# GEF-USB-B.net
KiCad netlist of a schematic drawn in EAGLE
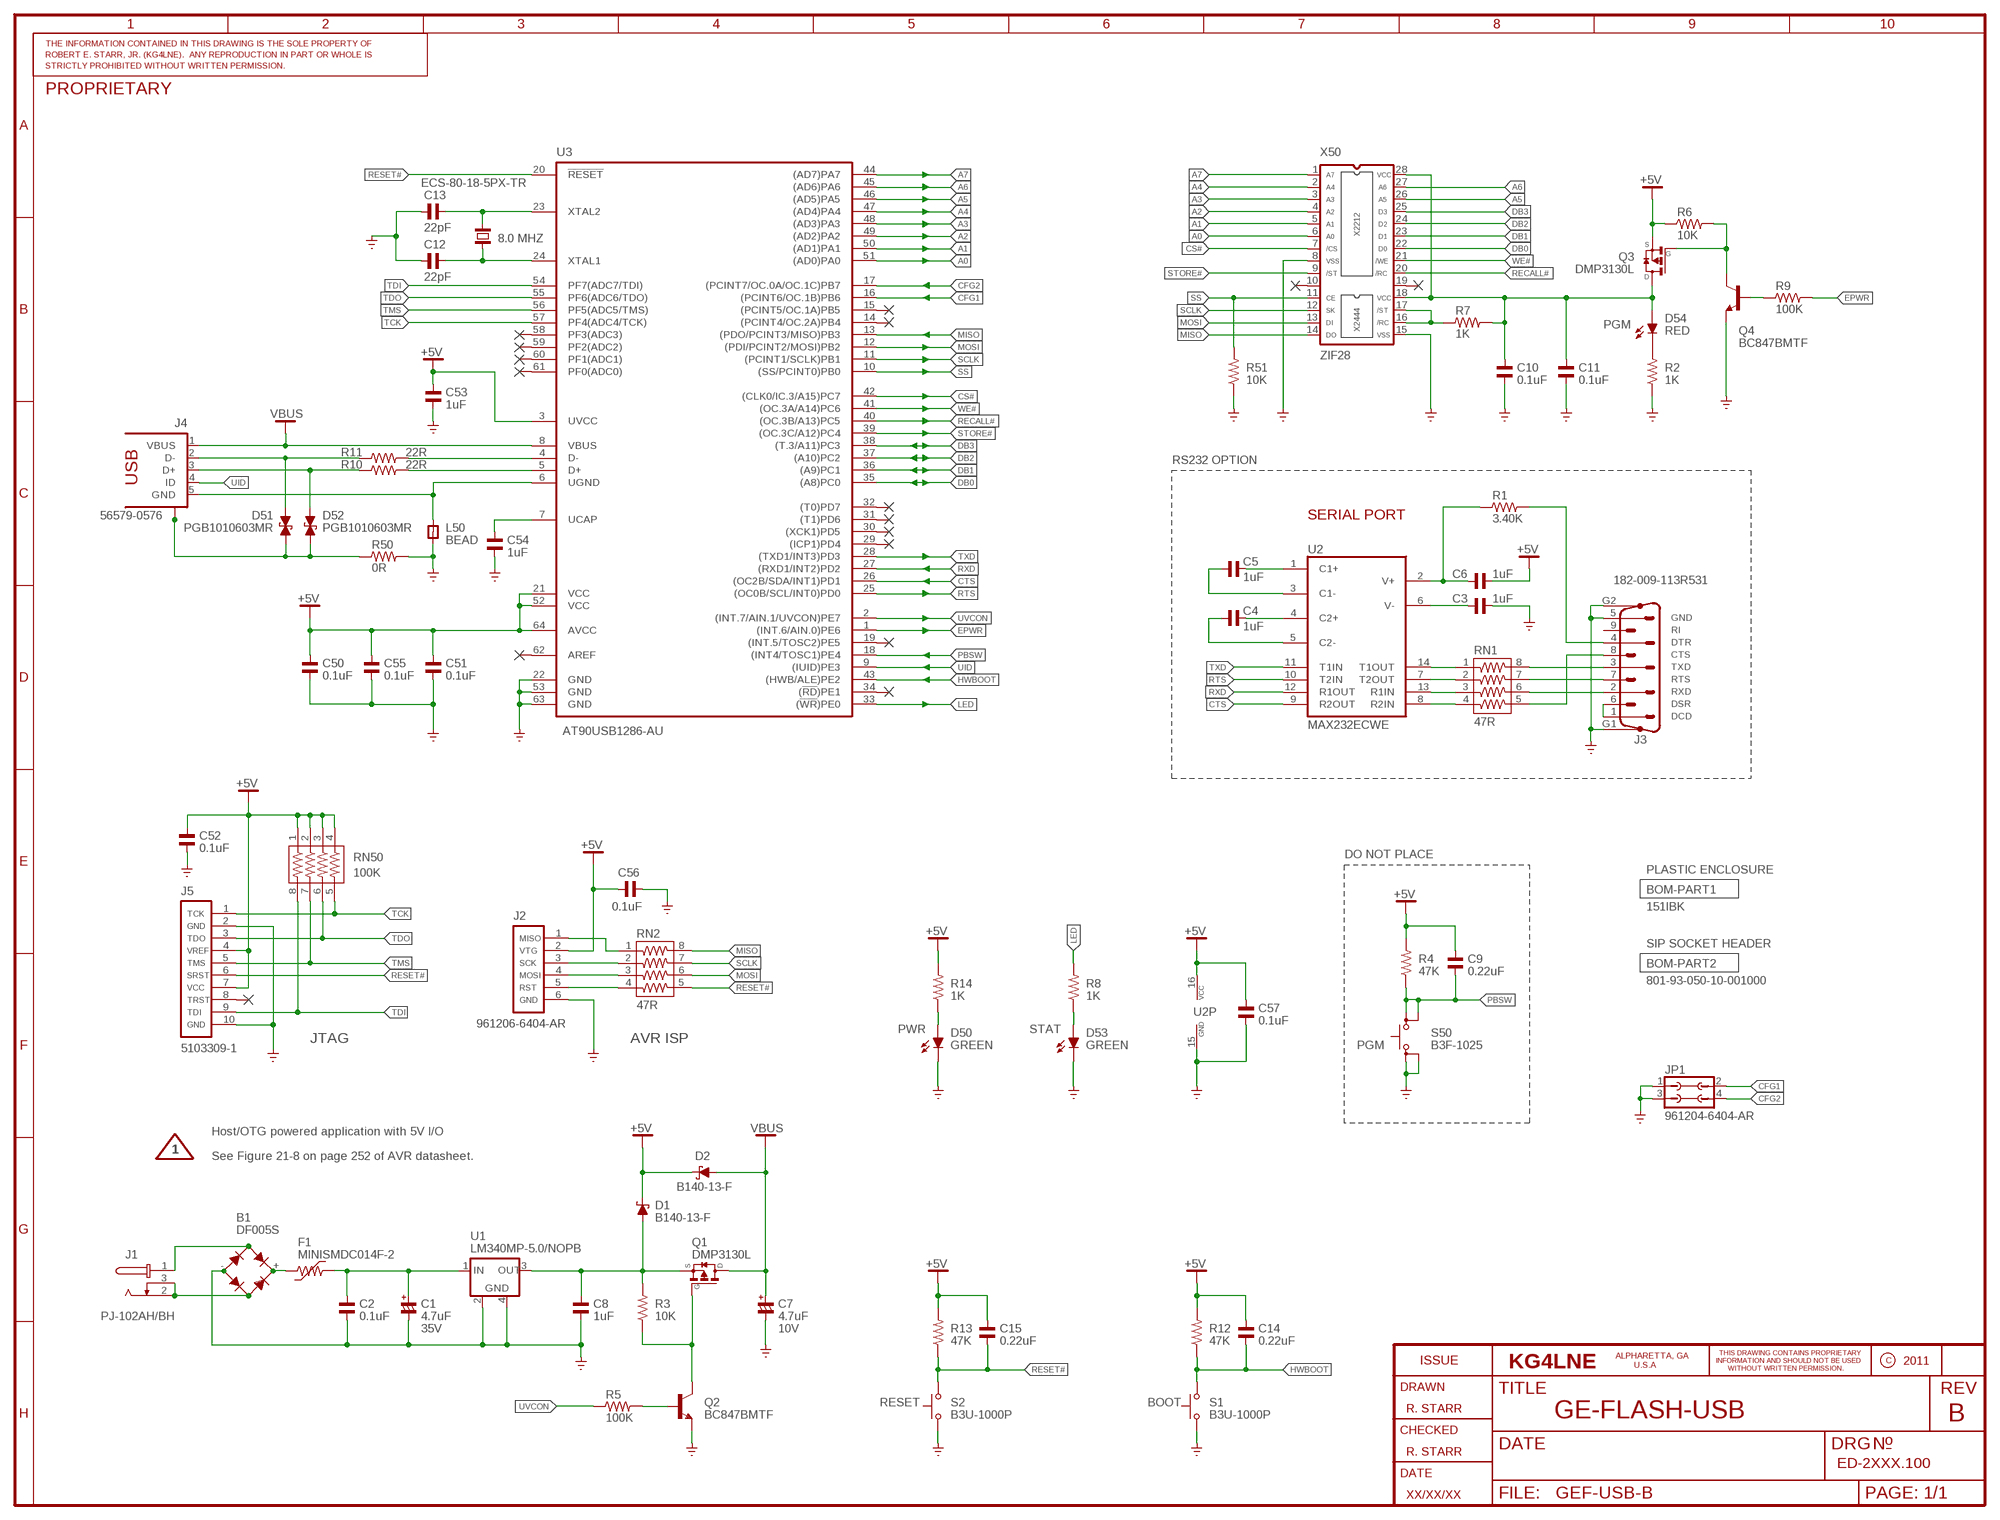
[diagram p0: schematic, sheet 1]

(export (version "E")
  (design (tool "Eeschema 10.0.6"))
  (components
    (comp (ref "B1")
      (value "DF005S")
      (footprint "eagle-import:DF-S")
      (libsource (lib "eagle-import") (part "DF-S"))
    )
    (comp (ref "C1")
      (value "4.7uF")
      (footprint "eagle-import:C7343_T")
      (fields (field (name "PARTNO") "TAJD475M035RNJ") (field (name "VOLT") "35V"))
      (libsource (lib "eagle-import") (part "CP_7343"))
    )
    (comp (ref "C2")
      (value "0.1uF")
      (footprint "eagle-import:C0805")
      (fields (field (name "PARTNO") "GCM21BR72A104KA37L"))
      (libsource (lib "eagle-import") (part "C_0805"))
    )
    (comp (ref "C3")
      (value "1uF")
      (footprint "eagle-import:C0805")
      (fields (field (name "PARTNO") "GCM21BR71E105KA56L"))
      (libsource (lib "eagle-import") (part "C_0805"))
    )
    (comp (ref "C4")
      (value "1uF")
      (footprint "eagle-import:C0805")
      (fields (field (name "PARTNO") "GCM21BR71E105KA56L"))
      (libsource (lib "eagle-import") (part "C_0805"))
    )
    (comp (ref "C5")
      (value "1uF")
      (footprint "eagle-import:C0805")
      (fields (field (name "PARTNO") "GCM21BR71E105KA56L"))
      (libsource (lib "eagle-import") (part "C_0805"))
    )
    (comp (ref "C6")
      (value "1uF")
      (footprint "eagle-import:C0805")
      (fields (field (name "PARTNO") "GCM21BR71E105KA56L"))
      (libsource (lib "eagle-import") (part "C_0805"))
    )
    (comp (ref "C7")
      (value "4.7uF")
      (footprint "eagle-import:C3528_T")
      (fields (field (name "PARTNO") "TAJB475K010RNJ") (field (name "VOLT") "10V"))
      (libsource (lib "eagle-import") (part "CP_3528"))
    )
    (comp (ref "C8")
      (value "1uF")
      (footprint "eagle-import:C0805")
      (fields (field (name "PARTNO") "GCM21BR71E105KA56L"))
      (libsource (lib "eagle-import") (part "C_0805"))
    )
    (comp (ref "C9")
      (value "0.22uF")
      (footprint "eagle-import:C0805")
      (fields (field (name "PARTNO") "GCM21BR71H224KA37L"))
      (libsource (lib "eagle-import") (part "C_0805"))
    )
    (comp (ref "C10")
      (value "0.1uF")
      (footprint "eagle-import:C0805")
      (fields (field (name "PARTNO") "GCM21BR72A104KA37L"))
      (libsource (lib "eagle-import") (part "C_0805"))
    )
    (comp (ref "C11")
      (value "0.1uF")
      (footprint "eagle-import:C0805")
      (fields (field (name "PARTNO") "GCM21BR72A104KA37L"))
      (libsource (lib "eagle-import") (part "C_0805"))
    )
    (comp (ref "C12")
      (value "22pF")
      (footprint "eagle-import:C0805")
      (fields (field (name "PARTNO") "GRM2195C2A220JZ01D"))
      (libsource (lib "eagle-import") (part "C_0805"))
    )
    (comp (ref "C13")
      (value "22pF")
      (footprint "eagle-import:C0805")
      (fields (field (name "PARTNO") "GRM2195C2A220JZ01D"))
      (libsource (lib "eagle-import") (part "C_0805"))
    )
    (comp (ref "C14")
      (value "0.22uF")
      (footprint "eagle-import:C0805")
      (fields (field (name "PARTNO") "GCM21BR71H224KA37L"))
      (libsource (lib "eagle-import") (part "C_0805"))
    )
    (comp (ref "C15")
      (value "0.22uF")
      (footprint "eagle-import:C0805")
      (fields (field (name "PARTNO") "GCM21BR71H224KA37L"))
      (libsource (lib "eagle-import") (part "C_0805"))
    )
    (comp (ref "C50")
      (value "0.1uF")
      (footprint "eagle-import:C0805")
      (fields (field (name "PARTNO") "GCM21BR72A104KA37L"))
      (libsource (lib "eagle-import") (part "C_0805"))
    )
    (comp (ref "C51")
      (value "0.1uF")
      (footprint "eagle-import:C0805")
      (fields (field (name "PARTNO") "GCM21BR72A104KA37L"))
      (libsource (lib "eagle-import") (part "C_0805"))
    )
    (comp (ref "C52")
      (value "0.1uF")
      (footprint "eagle-import:C0805")
      (fields (field (name "PARTNO") "GCM21BR72A104KA37L"))
      (libsource (lib "eagle-import") (part "C_0805"))
    )
    (comp (ref "C53")
      (value "1uF")
      (footprint "eagle-import:C0805")
      (fields (field (name "PARTNO") "GCM21BR71E105KA56L"))
      (libsource (lib "eagle-import") (part "C_0805"))
    )
    (comp (ref "C54")
      (value "1uF")
      (footprint "eagle-import:C0805")
      (fields (field (name "PARTNO") "GCM21BR71E105KA56L"))
      (libsource (lib "eagle-import") (part "C_0805"))
    )
    (comp (ref "C55")
      (value "0.1uF")
      (footprint "eagle-import:C0805")
      (fields (field (name "PARTNO") "GCM21BR72A104KA37L"))
      (libsource (lib "eagle-import") (part "C_0805"))
    )
    (comp (ref "C56")
      (value "0.1uF")
      (footprint "eagle-import:C0805")
      (fields (field (name "PARTNO") "GCM21BR72A104KA37L"))
      (libsource (lib "eagle-import") (part "C_0805"))
    )
    (comp (ref "C57")
      (value "0.1uF")
      (footprint "eagle-import:C0805")
      (fields (field (name "PARTNO") "GCM21BR72A104KA37L"))
      (libsource (lib "eagle-import") (part "C_0805"))
    )
    (comp (ref "D1")
      (value "B140-13-F")
      (footprint "eagle-import:SMA")
      (libsource (lib "eagle-import") (part "DIODE-SCHOTTKY-SMA"))
    )
    (comp (ref "D2")
      (value "B140-13-F")
      (footprint "eagle-import:SMA")
      (libsource (lib "eagle-import") (part "DIODE-SCHOTTKY-SMA"))
    )
    (comp (ref "D50")
      (value "GREEN")
      (footprint "eagle-import:LED3MM")
      (fields (field (name "LABEL") "PWR") (field (name "PARTNO") "TLHG4405"))
      (libsource (lib "eagle-import") (part "LED3MM"))
    )
    (comp (ref "D51")
      (value "PGB1010603MR")
      (footprint "eagle-import:PGB-0603")
      (libsource (lib "eagle-import") (part "PGB-0603"))
    )
    (comp (ref "D52")
      (value "PGB1010603MR")
      (footprint "eagle-import:PGB-0603")
      (libsource (lib "eagle-import") (part "PGB-0603"))
    )
    (comp (ref "D53")
      (value "GREEN")
      (footprint "eagle-import:LED3MM")
      (fields (field (name "LABEL") "STAT") (field (name "PARTNO") "TLHG4405"))
      (libsource (lib "eagle-import") (part "LED3MM"))
    )
    (comp (ref "D54")
      (value "RED")
      (footprint "eagle-import:LED3MM")
      (fields (field (name "LABEL") "PGM") (field (name "PARTNO") "TLHR4405"))
      (libsource (lib "eagle-import") (part "LED3MM"))
    )
    (comp (ref "F1")
      (value "MINISMDC014F-2")
      (footprint "eagle-import:F1812")
      (libsource (lib "eagle-import") (part "POLYSWITCH-F1812"))
    )
    (comp (ref "J1")
      (value "PJ-102AH/BH")
      (footprint "eagle-import:PJ-102XH")
      (fields (field (name "PARTNO") "PJ-102AH"))
      (libsource (lib "eagle-import") (part "PJ-102AH/BH"))
    )
    (comp (ref "J2")
      (value "961206-6404-AR")
      (footprint "eagle-import:HDR-MA03-2")
      (libsource (lib "eagle-import") (part "AVR-ISP6-MA03-2"))
    )
    (comp (ref "J3")
      (value "182-009-113R531")
      (footprint "eagle-import:NC182M9")
      (libsource (lib "eagle-import") (part "NC182M9-VS"))
    )
    (comp (ref "J4")
      (value "56579-0576")
      (footprint "eagle-import:56579-0576")
      (libsource (lib "eagle-import") (part "56579-0576"))
    )
    (comp (ref "J5")
      (value "5103309-1")
      (footprint "eagle-import:HDR-5103309-1")
      (libsource (lib "eagle-import") (part "AVR-JTAG10-5103309-1"))
    )
    (comp (ref "JP1")
      (value "961204-6404-AR")
      (footprint "eagle-import:JP2Q")
      (libsource (lib "eagle-import") (part "JP2Q"))
    )
    (comp (ref "L50")
      (value "BEAD")
      (footprint "eagle-import:L0805")
      (fields (field (name "PARTNO") "BLM21PG221SN1D"))
      (libsource (lib "eagle-import") (part "FB_0805"))
    )
    (comp (ref "Q1")
      (value "DMP3130L")
      (footprint "eagle-import:SOT23")
      (libsource (lib "eagle-import") (part "DMP3130L"))
    )
    (comp (ref "Q2")
      (value "BC847BMTF")
      (footprint "eagle-import:SOT23")
      (libsource (lib "eagle-import") (part "BC847SMDB"))
    )
    (comp (ref "Q3")
      (value "DMP3130L")
      (footprint "eagle-import:SOT23")
      (libsource (lib "eagle-import") (part "DMP3130L"))
    )
    (comp (ref "Q4")
      (value "BC847BMTF")
      (footprint "eagle-import:SOT23")
      (libsource (lib "eagle-import") (part "BC847SMDB"))
    )
    (comp (ref "R1")
      (value "3.40K")
      (footprint "eagle-import:R0805")
      (fields (field (name "PARTNO") "ERJ-6ENF3401V"))
      (libsource (lib "eagle-import") (part "R_0805"))
    )
    (comp (ref "R2")
      (value "1K")
      (footprint "eagle-import:R0805")
      (fields (field (name "PARTNO") "ERJ-6ENF1001V"))
      (libsource (lib "eagle-import") (part "R_0805"))
    )
    (comp (ref "R3")
      (value "10K")
      (footprint "eagle-import:R0805")
      (fields (field (name "PARTNO") "ERJ-6ENF1022V"))
      (libsource (lib "eagle-import") (part "R_0805"))
    )
    (comp (ref "R4")
      (value "47K")
      (footprint "eagle-import:R0805")
      (fields (field (name "PARTNO") "ERJ-6ENF4702V"))
      (libsource (lib "eagle-import") (part "R_0805"))
    )
    (comp (ref "R5")
      (value "100K")
      (footprint "eagle-import:R0805")
      (fields (field (name "PARTNO") "ERJ-6ENF1003V"))
      (libsource (lib "eagle-import") (part "R_0805"))
    )
    (comp (ref "R6")
      (value "10K")
      (footprint "eagle-import:R0805")
      (fields (field (name "PARTNO") "ERJ-6ENF1022V"))
      (libsource (lib "eagle-import") (part "R_0805"))
    )
    (comp (ref "R7")
      (value "1K")
      (footprint "eagle-import:R0805")
      (fields (field (name "PARTNO") "ERJ-6ENF1001V"))
      (libsource (lib "eagle-import") (part "R_0805"))
    )
    (comp (ref "R8")
      (value "1K")
      (footprint "eagle-import:R0805")
      (fields (field (name "PARTNO") "ERJ-6ENF1001V"))
      (libsource (lib "eagle-import") (part "R_0805"))
    )
    (comp (ref "R9")
      (value "100K")
      (footprint "eagle-import:R0805")
      (fields (field (name "PARTNO") "ERJ-6ENF1003V"))
      (libsource (lib "eagle-import") (part "R_0805"))
    )
    (comp (ref "R10")
      (value "22R")
      (footprint "eagle-import:R0805")
      (fields (field (name "PARTNO") "ERJ-6ENF22R1V"))
      (libsource (lib "eagle-import") (part "R_0805"))
    )
    (comp (ref "R11")
      (value "22R")
      (footprint "eagle-import:R0805")
      (fields (field (name "PARTNO") "ERJ-6ENF22R1V"))
      (libsource (lib "eagle-import") (part "R_0805"))
    )
    (comp (ref "R12")
      (value "47K")
      (footprint "eagle-import:R0805")
      (fields (field (name "PARTNO") "ERJ-6ENF4702V"))
      (libsource (lib "eagle-import") (part "R_0805"))
    )
    (comp (ref "R13")
      (value "47K")
      (footprint "eagle-import:R0805")
      (fields (field (name "PARTNO") "ERJ-6ENF4702V"))
      (libsource (lib "eagle-import") (part "R_0805"))
    )
    (comp (ref "R14")
      (value "1K")
      (footprint "eagle-import:R0805")
      (fields (field (name "PARTNO") "ERJ-6ENF1001V"))
      (libsource (lib "eagle-import") (part "R_0805"))
    )
    (comp (ref "R50")
      (value "0R")
      (footprint "eagle-import:R0805")
      (fields (field (name "PARTNO") "ERJ-6GEY0R00V"))
      (libsource (lib "eagle-import") (part "R_0805"))
    )
    (comp (ref "R51")
      (value "10K")
      (footprint "eagle-import:R0805")
      (fields (field (name "PARTNO") "ERJ-6ENF1022V"))
      (libsource (lib "eagle-import") (part "R_0805"))
    )
    (comp (ref "RN1")
      (value "47R")
      (footprint "eagle-import:744-8")
      (fields (field (name "PARTNO") "744C083470JTR"))
      (libsource (lib "eagle-import") (part "744-8"))
    )
    (comp (ref "RN2")
      (value "47R")
      (footprint "eagle-import:744-8")
      (fields (field (name "PARTNO") "744C083470JTR"))
      (libsource (lib "eagle-import") (part "744-8"))
    )
    (comp (ref "RN50")
      (value "100K")
      (footprint "eagle-import:744-8")
      (fields (field (name "PARTNO") "744C083104JPTR"))
      (libsource (lib "eagle-import") (part "744-8"))
    )
    (comp (ref "S1")
      (value "B3U-1000P")
      (footprint "eagle-import:B3U-1000P")
      (fields (field (name "LABEL") "BOOT"))
      (libsource (lib "eagle-import") (part "B3U-1000P"))
    )
    (comp (ref "S2")
      (value "B3U-1000P")
      (footprint "eagle-import:B3U-1000P")
      (fields (field (name "LABEL") "RESET"))
      (libsource (lib "eagle-import") (part "B3U-1000P"))
    )
    (comp (ref "S50")
      (value "B3F-1025")
      (footprint "eagle-import:B3F-10XX-B")
      (fields (field (name "LABEL") "PGM"))
      (libsource (lib "eagle-import") (part "10-XX-B"))
    )
    (comp (ref "U1")
      (value "LM340MP-5.0/NOPB")
      (footprint "eagle-import:SOT223")
      (libsource (lib "eagle-import") (part "LM340MP-5.0"))
    )
    (comp (ref "U2")
      (value "MAX232ECWE")
      (footprint "eagle-import:SO16W")
      (fields (field (name "PARTNO") "MAX232ECWE+"))
      (libsource (lib "eagle-import") (part "MAX232ECWE"))
    )
    (comp (ref "U3")
      (value "AT90USB1286-AU")
      (footprint "eagle-import:TQFP64A")
      (libsource (lib "eagle-import") (part "AT90USB646/647/1286/1287-MD"))
    )
    (comp (ref "X50")
      (value "ZIF28")
      (footprint "eagle-import:ZIF28")
      (fields (field (name "PARTNO") "28-6554-11"))
      (libsource (lib "eagle-import") (part "ZIF28"))
    )
    (comp (ref "Y1")
      (value "8.0 MHZ")
      (footprint "eagle-import:HC49UP")
      (fields (field (name "PARTNO") "ECS-80-18-5PX-TR"))
      (libsource (lib "eagle-import") (part "CRYTALHC49UP"))
    )
  )
  (nets
    (net (code "1") (name "+5V") (class "Default")
      (node (ref "C14") (pin "2") (pinfunction "2_2") (pintype "passive"))
      (node (ref "C15") (pin "2") (pinfunction "2_2") (pintype "passive"))
      (node (ref "C50") (pin "1") (pinfunction "1_1") (pintype "passive"))
      (node (ref "C51") (pin "2") (pinfunction "2_2") (pintype "passive"))
      (node (ref "C52") (pin "1") (pinfunction "1_1") (pintype "passive"))
      (node (ref "C53") (pin "2") (pinfunction "2_2") (pintype "passive"))
      (node (ref "C55") (pin "1") (pinfunction "1_1") (pintype "passive"))
      (node (ref "C56") (pin "2") (pinfunction "2_2") (pintype "passive"))
      (node (ref "C57") (pin "1") (pinfunction "1_1") (pintype "passive"))
      (node (ref "C6") (pin "1") (pinfunction "1_1") (pintype "passive"))
      (node (ref "C9") (pin "2") (pinfunction "2_2") (pintype "passive"))
      (node (ref "D1") (pin "C") (pinfunction "C_C") (pintype "passive"))
      (node (ref "D2") (pin "C") (pinfunction "C_C") (pintype "passive"))
      (node (ref "J2") (pin "2") (pinfunction "2_2") (pintype "passive"))
      (node (ref "J5") (pin "4") (pinfunction "4_4") (pintype "passive"))
      (node (ref "J5") (pin "7") (pinfunction "7_7") (pintype "passive"))
      (node (ref "Q3") (pin "2") (pinfunction "S_2") (pintype "passive"))
      (node (ref "R12") (pin "2") (pinfunction "2_2") (pintype "passive"))
      (node (ref "R13") (pin "2") (pinfunction "2_2") (pintype "passive"))
      (node (ref "R14") (pin "2") (pinfunction "2_2") (pintype "passive"))
      (node (ref "R4") (pin "2") (pinfunction "2_2") (pintype "passive"))
      (node (ref "R6") (pin "1") (pinfunction "1_1") (pintype "passive"))
      (node (ref "RN50") (pin "1") (pinfunction "1_1") (pintype "passive"))
      (node (ref "RN50") (pin "2") (pinfunction "2_2") (pintype "passive"))
      (node (ref "RN50") (pin "3") (pinfunction "3_3") (pintype "passive"))
      (node (ref "RN50") (pin "4") (pinfunction "4_4") (pintype "passive"))
      (node (ref "U2") (pin "16") (pinfunction "VCC_16") (pintype "power_in"))
      (node (ref "U3") (pin "21") (pinfunction "VCC_21") (pintype "power_in"))
      (node (ref "U3") (pin "3") (pinfunction "UVCC_3") (pintype "bidirectional"))
      (node (ref "U3") (pin "52") (pinfunction "VCC_52") (pintype "power_in"))
      (node (ref "U3") (pin "64") (pinfunction "AVCC_64") (pintype "bidirectional"))
    )
    (net (code "2") (name "A0") (class "Default")
      (node (ref "U3") (pin "51") (pinfunction "(AD0)PA0_51") (pintype "bidirectional"))
      (node (ref "X50") (pin "6") (pinfunction "6_6") (pintype "passive"))
    )
    (net (code "3") (name "A1") (class "Default")
      (node (ref "U3") (pin "50") (pinfunction "(AD1)PA1_50") (pintype "bidirectional"))
      (node (ref "X50") (pin "5") (pinfunction "5_5") (pintype "passive"))
    )
    (net (code "4") (name "A2") (class "Default")
      (node (ref "U3") (pin "49") (pinfunction "(AD2)PA2_49") (pintype "bidirectional"))
      (node (ref "X50") (pin "4") (pinfunction "4_4") (pintype "passive"))
    )
    (net (code "5") (name "A3") (class "Default")
      (node (ref "U3") (pin "48") (pinfunction "(AD3)PA3_48") (pintype "bidirectional"))
      (node (ref "X50") (pin "3") (pinfunction "3_3") (pintype "passive"))
    )
    (net (code "6") (name "A4") (class "Default")
      (node (ref "U3") (pin "47") (pinfunction "(AD4)PA4_47") (pintype "bidirectional"))
      (node (ref "X50") (pin "2") (pinfunction "2_2") (pintype "passive"))
    )
    (net (code "7") (name "A5") (class "Default")
      (node (ref "U3") (pin "46") (pinfunction "(AD5)PA5_46") (pintype "bidirectional"))
      (node (ref "X50") (pin "26") (pinfunction "26_26") (pintype "passive"))
    )
    (net (code "8") (name "A6") (class "Default")
      (node (ref "U3") (pin "45") (pinfunction "(AD6)PA6_45") (pintype "bidirectional"))
      (node (ref "X50") (pin "27") (pinfunction "27_27") (pintype "passive"))
    )
    (net (code "9") (name "A7") (class "Default")
      (node (ref "U3") (pin "44") (pinfunction "(AD7)PA7_44") (pintype "bidirectional"))
      (node (ref "X50") (pin "1") (pinfunction "1_1") (pintype "passive"))
    )
    (net (code "10") (name "CFG1") (class "Default")
      (node (ref "JP1") (pin "2") (pinfunction "2_2") (pintype "passive"))
      (node (ref "U3") (pin "16") (pinfunction "(PCINT6/OC.1B)PB6_16") (pintype "bidirectional"))
    )
    (net (code "11") (name "CFG2") (class "Default")
      (node (ref "JP1") (pin "4") (pinfunction "4_4") (pintype "passive"))
      (node (ref "U3") (pin "17") (pinfunction "(PCINT7/OC.0A/OC.1C)PB7_17") (pintype "bidirectional"))
    )
    (net (code "12") (name "CS#") (class "Default")
      (node (ref "U3") (pin "42") (pinfunction "(CLK0/IC.3/A15)PC7_42") (pintype "bidirectional"))
      (node (ref "X50") (pin "7") (pinfunction "7_7") (pintype "passive"))
    )
    (net (code "13") (name "CTS") (class "Default")
      (node (ref "U2") (pin "9") (pinfunction "R2OUT_9") (pintype "output"))
      (node (ref "U3") (pin "26") (pinfunction "(OC2B/SDA/INT1)PD1_26") (pintype "bidirectional"))
    )
    (net (code "14") (name "DB0") (class "Default")
      (node (ref "U3") (pin "35") (pinfunction "(A8)PC0_35") (pintype "bidirectional"))
      (node (ref "X50") (pin "22") (pinfunction "22_22") (pintype "passive"))
    )
    (net (code "15") (name "DB1") (class "Default")
      (node (ref "U3") (pin "36") (pinfunction "(A9)PC1_36") (pintype "bidirectional"))
      (node (ref "X50") (pin "23") (pinfunction "23_23") (pintype "passive"))
    )
    (net (code "16") (name "DB2") (class "Default")
      (node (ref "U3") (pin "37") (pinfunction "(A10)PC2_37") (pintype "bidirectional"))
      (node (ref "X50") (pin "24") (pinfunction "24_24") (pintype "passive"))
    )
    (net (code "17") (name "DB3") (class "Default")
      (node (ref "U3") (pin "38") (pinfunction "(T.3/A11)PC3_38") (pintype "bidirectional"))
      (node (ref "X50") (pin "25") (pinfunction "25_25") (pintype "passive"))
    )
    (net (code "18") (name "EPWR") (class "Default")
      (node (ref "R9") (pin "2") (pinfunction "2_2") (pintype "passive"))
      (node (ref "U3") (pin "1") (pinfunction "(INT.6/AIN.0)PE6_1") (pintype "bidirectional"))
    )
    (net (code "19") (name "GND_") (class "Default")
      (node (ref "B1") (pin "-") (pinfunction "-_-") (pintype "passive"))
      (node (ref "C1") (pin "-") (pinfunction "-_-") (pintype "passive"))
      (node (ref "C10") (pin "1") (pinfunction "1_1") (pintype "passive"))
      (node (ref "C11") (pin "1") (pinfunction "1_1") (pintype "passive"))
      (node (ref "C12") (pin "1") (pinfunction "1_1") (pintype "passive"))
      (node (ref "C13") (pin "1") (pinfunction "1_1") (pintype "passive"))
      (node (ref "C2") (pin "1") (pinfunction "1_1") (pintype "passive"))
      (node (ref "C3") (pin "1") (pinfunction "1_1") (pintype "passive"))
      (node (ref "C50") (pin "2") (pinfunction "2_2") (pintype "passive"))
      (node (ref "C51") (pin "1") (pinfunction "1_1") (pintype "passive"))
      (node (ref "C52") (pin "2") (pinfunction "2_2") (pintype "passive"))
      (node (ref "C53") (pin "1") (pinfunction "1_1") (pintype "passive"))
      (node (ref "C54") (pin "1") (pinfunction "1_1") (pintype "passive"))
      (node (ref "C55") (pin "2") (pinfunction "2_2") (pintype "passive"))
      (node (ref "C56") (pin "1") (pinfunction "1_1") (pintype "passive"))
      (node (ref "C57") (pin "2") (pinfunction "2_2") (pintype "passive"))
      (node (ref "C7") (pin "-") (pinfunction "-_-") (pintype "passive"))
      (node (ref "C8") (pin "2") (pinfunction "2_2") (pintype "passive"))
      (node (ref "D50") (pin "K") (pinfunction "C_K") (pintype "passive"))
      (node (ref "D53") (pin "K") (pinfunction "C_K") (pintype "passive"))
      (node (ref "J2") (pin "6") (pinfunction "6_6") (pintype "passive"))
      (node (ref "J3") (pin "5") (pinfunction "5_5") (pintype "passive"))
      (node (ref "J3") (pin "G1") (pinfunction "G1_G1") (pintype "passive"))
      (node (ref "J3") (pin "G2") (pinfunction "G2_G2") (pintype "passive"))
      (node (ref "J5") (pin "10") (pinfunction "10_10") (pintype "passive"))
      (node (ref "J5") (pin "2") (pinfunction "2_2") (pintype "passive"))
      (node (ref "JP1") (pin "1") (pinfunction "1_1") (pintype "passive"))
      (node (ref "JP1") (pin "3") (pinfunction "3_3") (pintype "passive"))
      (node (ref "L50") (pin "1") (pinfunction "1_1") (pintype "passive"))
      (node (ref "Q2") (pin "2") (pinfunction "E_2") (pintype "passive"))
      (node (ref "Q4") (pin "2") (pinfunction "E_2") (pintype "passive"))
      (node (ref "R2") (pin "1") (pinfunction "1_1") (pintype "passive"))
      (node (ref "R50") (pin "2") (pinfunction "2_2") (pintype "passive"))
      (node (ref "R51") (pin "1") (pinfunction "1_1") (pintype "passive"))
      (node (ref "S1") (pin "1") (pinfunction "P_1") (pintype "passive"))
      (node (ref "S2") (pin "1") (pinfunction "P_1") (pintype "passive"))
      (node (ref "S50") (pin "3") (pinfunction "P_3") (pintype "passive"))
      (node (ref "S50") (pin "4") (pinfunction "P1_4") (pintype "passive"))
      (node (ref "U1") (pin "2") (pinfunction "GND_2") (pintype "input"))
      (node (ref "U1") (pin "4") (pinfunction "GND1_4") (pintype "input"))
      (node (ref "U2") (pin "15") (pinfunction "GND_15") (pintype "power_in"))
      (node (ref "U3") (pin "22") (pinfunction "GND_22") (pintype "power_in"))
      (node (ref "U3") (pin "53") (pinfunction "GND_53") (pintype "power_in"))
      (node (ref "U3") (pin "63") (pinfunction "GND_63") (pintype "power_in"))
      (node (ref "X50") (pin "15") (pinfunction "15_15") (pintype "passive"))
      (node (ref "X50") (pin "8") (pinfunction "8_8") (pintype "passive"))
    )
    (net (code "20") (name "HWBOOT") (class "Default")
      (node (ref "C14") (pin "1") (pinfunction "1_1") (pintype "passive"))
      (node (ref "R12") (pin "1") (pinfunction "1_1") (pintype "passive"))
      (node (ref "S1") (pin "2") (pinfunction "S_2") (pintype "passive"))
      (node (ref "U3") (pin "43") (pinfunction "(HWB/ALE)PE2_43") (pintype "bidirectional"))
    )
    (net (code "21") (name "LED") (class "Default")
      (node (ref "R8") (pin "2") (pinfunction "2_2") (pintype "passive"))
      (node (ref "U3") (pin "33") (pinfunction "(~{WR})PE0_33") (pintype "bidirectional"))
    )
    (net (code "22") (name "MISO") (class "Default")
      (node (ref "RN2") (pin "8") (pinfunction "8_8") (pintype "passive"))
      (node (ref "U3") (pin "13") (pinfunction "(PDO/PCINT3/MISO)PB3_13") (pintype "bidirectional"))
      (node (ref "X50") (pin "14") (pinfunction "14_14") (pintype "passive"))
    )
    (net (code "23") (name "MOSI") (class "Default")
      (node (ref "RN2") (pin "6") (pinfunction "6_6") (pintype "passive"))
      (node (ref "U3") (pin "12") (pinfunction "(PDI/PCINT2/MOSI)PB2_12") (pintype "bidirectional"))
      (node (ref "X50") (pin "13") (pinfunction "13_13") (pintype "passive"))
    )
    (net (code "24") (name "Net-(B1-A1)") (class "Default")
      (node (ref "B1") (pin "AC1") (pinfunction "A1_AC1") (pintype "passive"))
      (node (ref "J1") (pin "1") (pinfunction "T_1") (pintype "passive"))
    )
    (net (code "25") (name "Net-(B1-A2)") (class "Default")
      (node (ref "B1") (pin "AC2") (pinfunction "A2_AC2") (pintype "passive"))
      (node (ref "J1") (pin "2") (pinfunction "S_2") (pintype "passive"))
      (node (ref "J1") (pin "3") (pinfunction "SS_3") (pintype "passive"))
    )
    (net (code "26") (name "Net-(B1-Pad+)") (class "Default")
      (node (ref "B1") (pin "+") (pinfunction "+_+") (pintype "passive"))
      (node (ref "F1") (pin "1") (pinfunction "1_1") (pintype "passive"))
    )
    (net (code "27") (name "Net-(D50-PadA)") (class "Default")
      (node (ref "D50") (pin "A") (pinfunction "A_A") (pintype "passive"))
      (node (ref "R14") (pin "1") (pinfunction "1_1") (pintype "passive"))
    )
    (net (code "28") (name "Net-(D51-Pad1)") (class "Default")
      (node (ref "D51") (pin "1") (pinfunction "1_1") (pintype "passive"))
      (node (ref "D52") (pin "1") (pinfunction "1_1") (pintype "passive"))
      (node (ref "J4") (pin "S1") (pinfunction "S1_S1") (pintype "passive"))
      (node (ref "J4") (pin "S2") (pinfunction "S2_S2") (pintype "passive"))
      (node (ref "J4") (pin "S3") (pinfunction "S3_S3") (pintype "passive"))
      (node (ref "J4") (pin "S4") (pinfunction "S4_S4") (pintype "passive"))
      (node (ref "R50") (pin "1") (pinfunction "1_1") (pintype "passive"))
    )
    (net (code "29") (name "Net-(D53-PadA)") (class "Default")
      (node (ref "D53") (pin "A") (pinfunction "A_A") (pintype "passive"))
      (node (ref "R8") (pin "1") (pinfunction "1_1") (pintype "passive"))
    )
    (net (code "30") (name "Net-(D54-C)") (class "Default")
      (node (ref "D54") (pin "K") (pinfunction "C_K") (pintype "passive"))
      (node (ref "R2") (pin "2") (pinfunction "2_2") (pintype "passive"))
    )
    (net (code "31") (name "Net-(J2-Pad1)") (class "Default")
      (node (ref "J2") (pin "1") (pinfunction "1_1") (pintype "passive"))
      (node (ref "RN2") (pin "1") (pinfunction "1_1") (pintype "passive"))
    )
    (net (code "32") (name "Net-(J2-Pad3)") (class "Default")
      (node (ref "J2") (pin "3") (pinfunction "3_3") (pintype "passive"))
      (node (ref "RN2") (pin "2") (pinfunction "2_2") (pintype "passive"))
    )
    (net (code "33") (name "Net-(J2-Pad4)") (class "Default")
      (node (ref "J2") (pin "4") (pinfunction "4_4") (pintype "passive"))
      (node (ref "RN2") (pin "3") (pinfunction "3_3") (pintype "passive"))
    )
    (net (code "34") (name "Net-(J2-Pad5)") (class "Default")
      (node (ref "J2") (pin "5") (pinfunction "5_5") (pintype "passive"))
      (node (ref "RN2") (pin "4") (pinfunction "4_4") (pintype "passive"))
    )
    (net (code "35") (name "Net-(J3-Pad1)") (class "Default")
      (node (ref "J3") (pin "1") (pinfunction "1_1") (pintype "passive"))
      (node (ref "J3") (pin "6") (pinfunction "6_6") (pintype "passive"))
    )
    (net (code "36") (name "Net-(J3-Pad2)") (class "Default")
      (node (ref "J3") (pin "2") (pinfunction "2_2") (pintype "passive"))
      (node (ref "RN1") (pin "6") (pinfunction "6_6") (pintype "passive"))
    )
    (net (code "37") (name "Net-(J3-Pad3)") (class "Default")
      (node (ref "J3") (pin "3") (pinfunction "3_3") (pintype "passive"))
      (node (ref "RN1") (pin "8") (pinfunction "8_8") (pintype "passive"))
    )
    (net (code "38") (name "Net-(J3-Pad4)") (class "Default")
      (node (ref "J3") (pin "4") (pinfunction "4_4") (pintype "passive"))
      (node (ref "R1") (pin "2") (pinfunction "2_2") (pintype "passive"))
    )
    (net (code "39") (name "Net-(J3-Pad7)") (class "Default")
      (node (ref "J3") (pin "7") (pinfunction "7_7") (pintype "passive"))
      (node (ref "RN1") (pin "7") (pinfunction "7_7") (pintype "passive"))
    )
    (net (code "40") (name "Net-(J3-Pad8)") (class "Default")
      (node (ref "J3") (pin "8") (pinfunction "8_8") (pintype "passive"))
      (node (ref "RN1") (pin "5") (pinfunction "5_5") (pintype "passive"))
    )
    (net (code "41") (name "Net-(J4-D+)") (class "Default")
      (node (ref "D52") (pin "2") (pinfunction "2_2") (pintype "passive"))
      (node (ref "J4") (pin "3") (pinfunction "D+_3") (pintype "passive"))
      (node (ref "R10") (pin "1") (pinfunction "1_1") (pintype "passive"))
    )
    (net (code "42") (name "Net-(J4-D-)") (class "Default")
      (node (ref "D51") (pin "2") (pinfunction "2_2") (pintype "passive"))
      (node (ref "J4") (pin "2") (pinfunction "D-_2") (pintype "passive"))
      (node (ref "R11") (pin "1") (pinfunction "1_1") (pintype "passive"))
    )
    (net (code "43") (name "Net-(J4-GND)") (class "Default")
      (node (ref "J4") (pin "5") (pinfunction "GND_5") (pintype "passive"))
      (node (ref "L50") (pin "2") (pinfunction "2_2") (pintype "passive"))
      (node (ref "U3") (pin "6") (pinfunction "UGND_6") (pintype "bidirectional"))
    )
    (net (code "44") (name "Net-(Q1-G)") (class "Default")
      (node (ref "Q1") (pin "1") (pinfunction "G_1") (pintype "passive"))
      (node (ref "Q2") (pin "3") (pinfunction "C_3") (pintype "passive"))
      (node (ref "R3") (pin "1") (pinfunction "1_1") (pintype "passive"))
    )
    (net (code "45") (name "Net-(Q1-S)") (class "Default")
      (node (ref "C8") (pin "1") (pinfunction "1_1") (pintype "passive"))
      (node (ref "D1") (pin "A") (pinfunction "A_A") (pintype "passive"))
      (node (ref "Q1") (pin "2") (pinfunction "S_2") (pintype "passive"))
      (node (ref "R3") (pin "2") (pinfunction "2_2") (pintype "passive"))
      (node (ref "U1") (pin "3") (pinfunction "OUT_3") (pintype "passive"))
    )
    (net (code "46") (name "Net-(Q2-B)") (class "Default")
      (node (ref "Q2") (pin "1") (pinfunction "B_1") (pintype "passive"))
      (node (ref "R5") (pin "2") (pinfunction "2_2") (pintype "passive"))
    )
    (net (code "47") (name "Net-(Q3-D)") (class "Default")
      (node (ref "C10") (pin "2") (pinfunction "2_2") (pintype "passive"))
      (node (ref "C11") (pin "2") (pinfunction "2_2") (pintype "passive"))
      (node (ref "D54") (pin "A") (pinfunction "A_A") (pintype "passive"))
      (node (ref "Q3") (pin "3") (pinfunction "D_3") (pintype "passive"))
      (node (ref "R7") (pin "2") (pinfunction "2_2") (pintype "passive"))
      (node (ref "X50") (pin "18") (pinfunction "18_18") (pintype "passive"))
      (node (ref "X50") (pin "28") (pinfunction "28_28") (pintype "passive"))
    )
    (net (code "48") (name "Net-(Q3-G)") (class "Default")
      (node (ref "Q3") (pin "1") (pinfunction "G_1") (pintype "passive"))
      (node (ref "Q4") (pin "3") (pinfunction "C_3") (pintype "passive"))
      (node (ref "R6") (pin "2") (pinfunction "2_2") (pintype "passive"))
    )
    (net (code "49") (name "Net-(Q4-B)") (class "Default")
      (node (ref "Q4") (pin "1") (pinfunction "B_1") (pintype "passive"))
      (node (ref "R9") (pin "1") (pinfunction "1_1") (pintype "passive"))
    )
    (net (code "50") (name "Net-(R7-Pad1)") (class "Default")
      (node (ref "R7") (pin "1") (pinfunction "1_1") (pintype "passive"))
      (node (ref "X50") (pin "16") (pinfunction "16_16") (pintype "passive"))
      (node (ref "X50") (pin "17") (pinfunction "17_17") (pintype "passive"))
    )
    (net (code "51") (name "Net-(U1-IN)") (class "Default")
      (node (ref "C1") (pin "+") (pinfunction "+_+") (pintype "passive"))
      (node (ref "C2") (pin "2") (pinfunction "2_2") (pintype "passive"))
      (node (ref "F1") (pin "2") (pinfunction "2_2") (pintype "passive"))
      (node (ref "U1") (pin "1") (pinfunction "IN_1") (pintype "input"))
    )
    (net (code "52") (name "Net-(U2A-C1+)") (class "Default")
      (node (ref "C5") (pin "1") (pinfunction "1_1") (pintype "passive"))
      (node (ref "U2") (pin "1") (pinfunction "C1+_1") (pintype "bidirectional"))
    )
    (net (code "53") (name "Net-(U2A-C1-)") (class "Default")
      (node (ref "C5") (pin "2") (pinfunction "2_2") (pintype "passive"))
      (node (ref "U2") (pin "3") (pinfunction "C1-_3") (pintype "bidirectional"))
    )
    (net (code "54") (name "Net-(U2A-C2+)") (class "Default")
      (node (ref "C4") (pin "1") (pinfunction "1_1") (pintype "passive"))
      (node (ref "U2") (pin "4") (pinfunction "C2+_4") (pintype "bidirectional"))
    )
    (net (code "55") (name "Net-(U2A-C2-)") (class "Default")
      (node (ref "C4") (pin "2") (pinfunction "2_2") (pintype "passive"))
      (node (ref "U2") (pin "5") (pinfunction "C2-_5") (pintype "bidirectional"))
    )
    (net (code "56") (name "Net-(U2A-R1IN)") (class "Default")
      (node (ref "RN1") (pin "3") (pinfunction "3_3") (pintype "passive"))
      (node (ref "U2") (pin "13") (pinfunction "R1IN_13") (pintype "input"))
    )
    (net (code "57") (name "Net-(U2A-R2IN)") (class "Default")
      (node (ref "RN1") (pin "4") (pinfunction "4_4") (pintype "passive"))
      (node (ref "U2") (pin "8") (pinfunction "R2IN_8") (pintype "input"))
    )
    (net (code "58") (name "Net-(U2A-T1OUT)") (class "Default")
      (node (ref "RN1") (pin "1") (pinfunction "1_1") (pintype "passive"))
      (node (ref "U2") (pin "14") (pinfunction "T1OUT_14") (pintype "output"))
    )
    (net (code "59") (name "Net-(U2A-T2OUT)") (class "Default")
      (node (ref "RN1") (pin "2") (pinfunction "2_2") (pintype "passive"))
      (node (ref "U2") (pin "7") (pinfunction "T2OUT_7") (pintype "output"))
    )
    (net (code "60") (name "Net-(U2A-V+)") (class "Default")
      (node (ref "C6") (pin "2") (pinfunction "2_2") (pintype "passive"))
      (node (ref "R1") (pin "1") (pinfunction "1_1") (pintype "passive"))
      (node (ref "U2") (pin "2") (pinfunction "V+_2") (pintype "bidirectional"))
    )
    (net (code "61") (name "Net-(U2A-V-)") (class "Default")
      (node (ref "C3") (pin "2") (pinfunction "2_2") (pintype "passive"))
      (node (ref "U2") (pin "6") (pinfunction "V-_6") (pintype "bidirectional"))
    )
    (net (code "62") (name "Net-(U3-D+)") (class "Default")
      (node (ref "R10") (pin "2") (pinfunction "2_2") (pintype "passive"))
      (node (ref "U3") (pin "5") (pinfunction "D+_5") (pintype "bidirectional"))
    )
    (net (code "63") (name "Net-(U3-D-)") (class "Default")
      (node (ref "R11") (pin "2") (pinfunction "2_2") (pintype "passive"))
      (node (ref "U3") (pin "4") (pinfunction "D-_4") (pintype "bidirectional"))
    )
    (net (code "64") (name "Net-(U3-UCAP)") (class "Default")
      (node (ref "C54") (pin "2") (pinfunction "2_2") (pintype "passive"))
      (node (ref "U3") (pin "7") (pinfunction "UCAP_7") (pintype "bidirectional"))
    )
    (net (code "65") (name "Net-(U3-XTAL1)") (class "Default")
      (node (ref "C12") (pin "2") (pinfunction "2_2") (pintype "passive"))
      (node (ref "U3") (pin "24") (pinfunction "XTAL1_24") (pintype "bidirectional"))
      (node (ref "Y1") (pin "1") (pinfunction "1_1") (pintype "passive"))
    )
    (net (code "66") (name "Net-(U3-XTAL2)") (class "Default")
      (node (ref "C13") (pin "2") (pinfunction "2_2") (pintype "passive"))
      (node (ref "U3") (pin "23") (pinfunction "XTAL2_23") (pintype "bidirectional"))
      (node (ref "Y1") (pin "2") (pinfunction "2_2") (pintype "passive"))
    )
    (net (code "67") (name "PBSW") (class "Default")
      (node (ref "C9") (pin "1") (pinfunction "1_1") (pintype "passive"))
      (node (ref "R4") (pin "1") (pinfunction "1_1") (pintype "passive"))
      (node (ref "S50") (pin "1") (pinfunction "S_1") (pintype "passive"))
      (node (ref "S50") (pin "2") (pinfunction "S1_2") (pintype "passive"))
      (node (ref "U3") (pin "18") (pinfunction "(INT4/TOSC1)PE4_18") (pintype "bidirectional"))
    )
    (net (code "68") (name "RECALL#") (class "Default")
      (node (ref "U3") (pin "40") (pinfunction "(OC.3B/A13)PC5_40") (pintype "bidirectional"))
      (node (ref "X50") (pin "20") (pinfunction "20_20") (pintype "passive"))
    )
    (net (code "69") (name "RESET#") (class "Default")
      (node (ref "C15") (pin "1") (pinfunction "1_1") (pintype "passive"))
      (node (ref "J5") (pin "6") (pinfunction "6_6") (pintype "passive"))
      (node (ref "R13") (pin "1") (pinfunction "1_1") (pintype "passive"))
      (node (ref "RN2") (pin "5") (pinfunction "5_5") (pintype "passive"))
      (node (ref "S2") (pin "2") (pinfunction "S_2") (pintype "passive"))
      (node (ref "U3") (pin "20") (pinfunction "~{RESET}_20") (pintype "input"))
    )
    (net (code "70") (name "RTS") (class "Default")
      (node (ref "U2") (pin "10") (pinfunction "T2IN_10") (pintype "input"))
      (node (ref "U3") (pin "25") (pinfunction "(OC0B/SCL/INT0)PD0_25") (pintype "bidirectional"))
    )
    (net (code "71") (name "RXD") (class "Default")
      (node (ref "U2") (pin "12") (pinfunction "R1OUT_12") (pintype "output"))
      (node (ref "U3") (pin "27") (pinfunction "(RXD1/INT2)PD2_27") (pintype "bidirectional"))
    )
    (net (code "72") (name "SCLK") (class "Default")
      (node (ref "RN2") (pin "7") (pinfunction "7_7") (pintype "passive"))
      (node (ref "U3") (pin "11") (pinfunction "(PCINT1/SCLK)PB1_11") (pintype "bidirectional"))
      (node (ref "X50") (pin "12") (pinfunction "12_12") (pintype "passive"))
    )
    (net (code "73") (name "SS") (class "Default")
      (node (ref "R51") (pin "2") (pinfunction "2_2") (pintype "passive"))
      (node (ref "U3") (pin "10") (pinfunction "(SS/PCINT0)PB0_10") (pintype "bidirectional"))
      (node (ref "X50") (pin "11") (pinfunction "11_11") (pintype "passive"))
    )
    (net (code "74") (name "STORE#") (class "Default")
      (node (ref "U3") (pin "39") (pinfunction "(OC.3C/A12)PC4_39") (pintype "bidirectional"))
      (node (ref "X50") (pin "9") (pinfunction "9_9") (pintype "passive"))
    )
    (net (code "75") (name "TCK") (class "Default")
      (node (ref "J5") (pin "1") (pinfunction "1_1") (pintype "passive"))
      (node (ref "RN50") (pin "5") (pinfunction "5_5") (pintype "passive"))
      (node (ref "U3") (pin "57") (pinfunction "PF4(ADC4/TCK)_57") (pintype "bidirectional"))
    )
    (net (code "76") (name "TDI") (class "Default")
      (node (ref "J5") (pin "9") (pinfunction "9_9") (pintype "passive"))
      (node (ref "RN50") (pin "8") (pinfunction "8_8") (pintype "passive"))
      (node (ref "U3") (pin "54") (pinfunction "PF7(ADC7/TDI)_54") (pintype "bidirectional"))
    )
    (net (code "77") (name "TDO") (class "Default")
      (node (ref "J5") (pin "3") (pinfunction "3_3") (pintype "passive"))
      (node (ref "RN50") (pin "6") (pinfunction "6_6") (pintype "passive"))
      (node (ref "U3") (pin "55") (pinfunction "PF6(ADC6/TDO)_55") (pintype "bidirectional"))
    )
    (net (code "78") (name "TMS") (class "Default")
      (node (ref "J5") (pin "5") (pinfunction "5_5") (pintype "passive"))
      (node (ref "RN50") (pin "7") (pinfunction "7_7") (pintype "passive"))
      (node (ref "U3") (pin "56") (pinfunction "PF5(ADC5/TMS)_56") (pintype "bidirectional"))
    )
    (net (code "79") (name "TXD") (class "Default")
      (node (ref "U2") (pin "11") (pinfunction "T1IN_11") (pintype "input"))
      (node (ref "U3") (pin "28") (pinfunction "(TXD1/INT3)PD3_28") (pintype "bidirectional"))
    )
    (net (code "80") (name "UID") (class "Default")
      (node (ref "J4") (pin "4") (pinfunction "ID_4") (pintype "passive"))
      (node (ref "U3") (pin "9") (pinfunction "(IUID)PE3_9") (pintype "bidirectional"))
    )
    (net (code "81") (name "UVCON") (class "Default")
      (node (ref "R5") (pin "1") (pinfunction "1_1") (pintype "passive"))
      (node (ref "U3") (pin "2") (pinfunction "(INT.7/AIN.1/UVCON)PE7_2") (pintype "bidirectional"))
    )
    (net (code "82") (name "VBUS") (class "Default")
      (node (ref "C7") (pin "+") (pinfunction "+_+") (pintype "passive"))
      (node (ref "D2") (pin "A") (pinfunction "A_A") (pintype "passive"))
      (node (ref "J4") (pin "1") (pinfunction "VBUS_1") (pintype "passive"))
      (node (ref "Q1") (pin "3") (pinfunction "D_3") (pintype "passive"))
      (node (ref "U3") (pin "8") (pinfunction "VBUS_8") (pintype "bidirectional"))
    )
    (net (code "83") (name "WE#") (class "Default")
      (node (ref "U3") (pin "41") (pinfunction "(OC.3A/A14)PC6_41") (pintype "bidirectional"))
      (node (ref "X50") (pin "21") (pinfunction "21_21") (pintype "passive"))
    )
    (net (code "84") (name "unconnected-(J3-Pad9)") (class "Default")
      (node (ref "J3") (pin "9") (pinfunction "9_9") (pintype "passive"))
    )
    (net (code "85") (name "unconnected-(J5-Pad8)") (class "Default")
      (node (ref "J5") (pin "8") (pinfunction "8_8") (pintype "passive"))
    )
    (net (code "86") (name "unconnected-(U3-(ICP1)PD4-Pad29)") (class "Default")
      (node (ref "U3") (pin "29") (pinfunction "(ICP1)PD4_29") (pintype "bidirectional"))
    )
    (net (code "87") (name "unconnected-(U3-(INT.5{slash}TOSC2)PE5-Pad19)") (class "Default")
      (node (ref "U3") (pin "19") (pinfunction "(INT.5/TOSC2)PE5_19") (pintype "bidirectional"))
    )
    (net (code "88") (name "unconnected-(U3-(PCINT4{slash}OC.2A)PB4-Pad14)") (class "Default")
      (node (ref "U3") (pin "14") (pinfunction "(PCINT4/OC.2A)PB4_14") (pintype "bidirectional"))
    )
    (net (code "89") (name "unconnected-(U3-(PCINT5{slash}OC.1A)PB5-Pad15)") (class "Default")
      (node (ref "U3") (pin "15") (pinfunction "(PCINT5/OC.1A)PB5_15") (pintype "bidirectional"))
    )
    (net (code "90") (name "unconnected-(U3-(T0)PD7-Pad32)") (class "Default")
      (node (ref "U3") (pin "32") (pinfunction "(T0)PD7_32") (pintype "bidirectional"))
    )
    (net (code "91") (name "unconnected-(U3-(T1)PD6-Pad31)") (class "Default")
      (node (ref "U3") (pin "31") (pinfunction "(T1)PD6_31") (pintype "bidirectional"))
    )
    (net (code "92") (name "unconnected-(U3-(XCK1)PD5-Pad30)") (class "Default")
      (node (ref "U3") (pin "30") (pinfunction "(XCK1)PD5_30") (pintype "bidirectional"))
    )
    (net (code "93") (name "unconnected-(U3-(~{RD})PE1-Pad34)") (class "Default")
      (node (ref "U3") (pin "34") (pinfunction "(~{RD})PE1_34") (pintype "bidirectional"))
    )
    (net (code "94") (name "unconnected-(U3-AREF-Pad62)") (class "Default")
      (node (ref "U3") (pin "62") (pinfunction "AREF_62") (pintype "bidirectional"))
    )
    (net (code "95") (name "unconnected-(U3-PF0(ADC0)-Pad61)") (class "Default")
      (node (ref "U3") (pin "61") (pinfunction "PF0(ADC0)_61") (pintype "bidirectional"))
    )
    (net (code "96") (name "unconnected-(U3-PF1(ADC1)-Pad60)") (class "Default")
      (node (ref "U3") (pin "60") (pinfunction "PF1(ADC1)_60") (pintype "bidirectional"))
    )
    (net (code "97") (name "unconnected-(U3-PF2(ADC2)-Pad59)") (class "Default")
      (node (ref "U3") (pin "59") (pinfunction "PF2(ADC2)_59") (pintype "bidirectional"))
    )
    (net (code "98") (name "unconnected-(U3-PF3(ADC3)-Pad58)") (class "Default")
      (node (ref "U3") (pin "58") (pinfunction "PF3(ADC3)_58") (pintype "bidirectional"))
    )
    (net (code "99") (name "unconnected-(X50-Pad10)") (class "Default")
      (node (ref "X50") (pin "10") (pinfunction "10_10") (pintype "passive"))
    )
    (net (code "100") (name "unconnected-(X50-Pad19)") (class "Default")
      (node (ref "X50") (pin "19") (pinfunction "19_19") (pintype "passive"))
    )
  )
)
